# 03_cizgi_sensoru.net
KiCad netlist of a schematic drawn in EAGLE
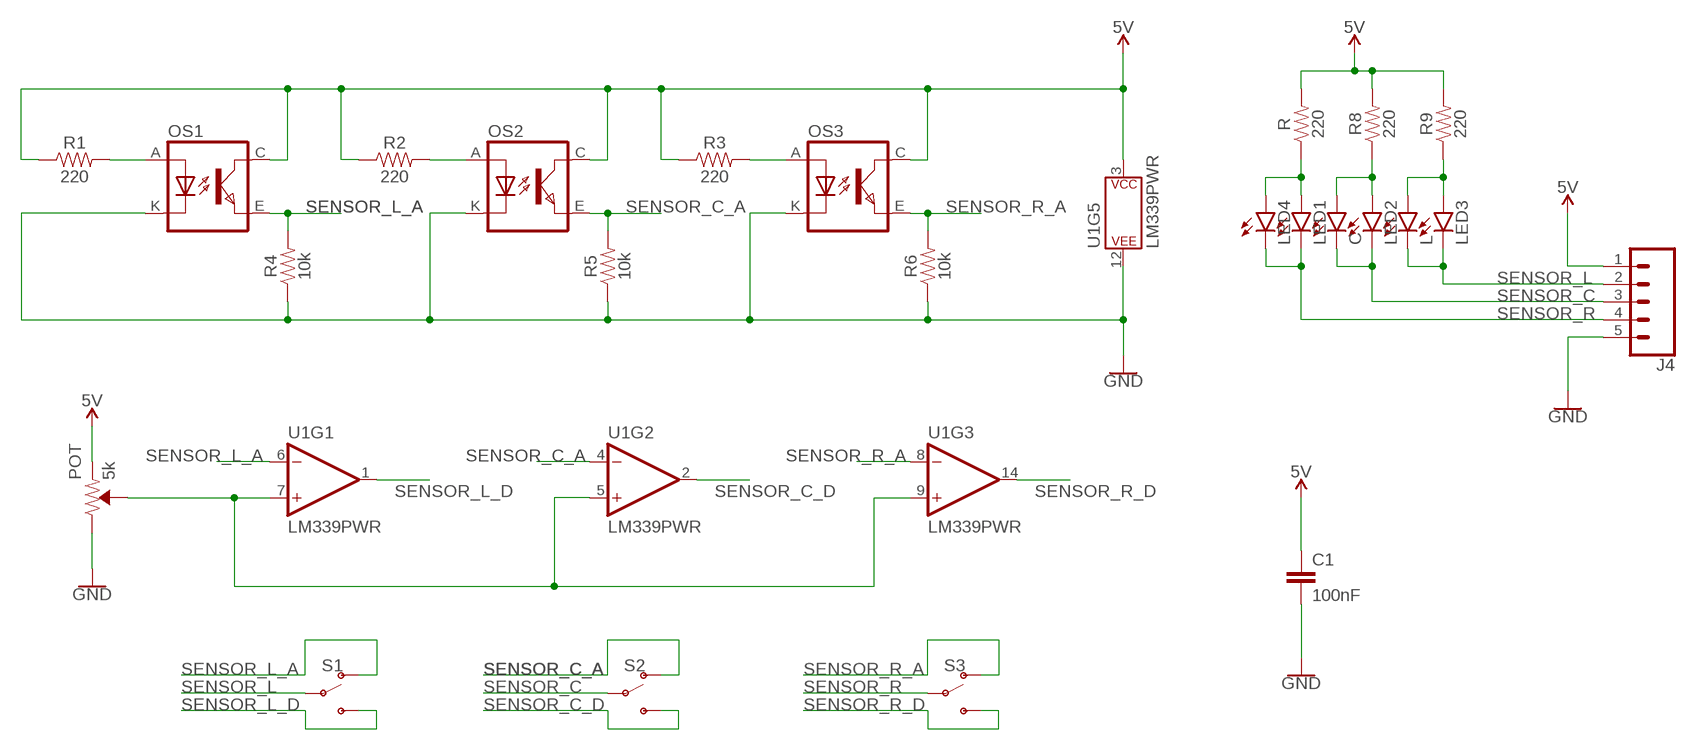
[diagram p0: schematic, sheet 1]

(export (version "E")
  (design (tool "Eeschema 10.0.6"))
  (components
    (comp (ref "C")
      (value "LEDSML0805")
      (footprint "eagle-import:SML0805")
      (libsource (lib "eagle-import") (part "LEDSML0805"))
    )
    (comp (ref "C1")
      (value "100nF")
      (footprint "eagle-import:0805")
      (libsource (lib "eagle-import") (part "0.33UF/330NF-0805-50V-10%"))
    )
    (comp (ref "J4")
      (value "CONN_05")
      (footprint "eagle-import:1X05")
      (libsource (lib "eagle-import") (part "CONN_05"))
    )
    (comp (ref "L")
      (value "LEDSML0805")
      (footprint "eagle-import:SML0805")
      (libsource (lib "eagle-import") (part "LEDSML0805"))
    )
    (comp (ref "LED1")
      (value "LEDSML0805")
      (footprint "eagle-import:SML0805")
      (libsource (lib "eagle-import") (part "LEDSML0805"))
    )
    (comp (ref "LED2")
      (value "LEDSML0805")
      (footprint "eagle-import:SML0805")
      (libsource (lib "eagle-import") (part "LEDSML0805"))
    )
    (comp (ref "LED3")
      (value "LEDSML0805")
      (footprint "eagle-import:SML0805")
      (libsource (lib "eagle-import") (part "LEDSML0805"))
    )
    (comp (ref "LED4")
      (value "LEDSML0805")
      (footprint "eagle-import:SML0805")
      (libsource (lib "eagle-import") (part "LEDSML0805"))
    )
    (comp (ref "OS1")
      (value "TCRT5000")
      (footprint "eagle-import:TCRT5000")
      (libsource (lib "eagle-import") (part "TCRT5000"))
    )
    (comp (ref "OS2")
      (value "TCRT5000")
      (footprint "eagle-import:TCRT5000")
      (libsource (lib "eagle-import") (part "TCRT5000"))
    )
    (comp (ref "OS3")
      (value "TCRT5000")
      (footprint "eagle-import:TCRT5000")
      (libsource (lib "eagle-import") (part "TCRT5000"))
    )
    (comp (ref "POT")
      (value "5k")
      (footprint "eagle-import:TRIMPOT-SMD-5MM")
      (libsource (lib "eagle-import") (part "TRIMPOT-SMD-5MM-CLOSED-1/4W-20%"))
    )
    (comp (ref "R")
      (value "220")
      (footprint "eagle-import:0805")
      (libsource (lib "eagle-import") (part "0.22OHM-0805-1/4W-1%"))
    )
    (comp (ref "R1")
      (value "220")
      (footprint "eagle-import:0805")
      (libsource (lib "eagle-import") (part "0.22OHM-0805-1/4W-1%"))
    )
    (comp (ref "R2")
      (value "220")
      (footprint "eagle-import:0805")
      (libsource (lib "eagle-import") (part "0.22OHM-0805-1/4W-1%"))
    )
    (comp (ref "R3")
      (value "220")
      (footprint "eagle-import:0805")
      (libsource (lib "eagle-import") (part "0.22OHM-0805-1/4W-1%"))
    )
    (comp (ref "R4")
      (value "10k")
      (footprint "eagle-import:0805")
      (libsource (lib "eagle-import") (part "0.22OHM-0805-1/4W-1%"))
    )
    (comp (ref "R5")
      (value "10k")
      (footprint "eagle-import:0805")
      (libsource (lib "eagle-import") (part "0.22OHM-0805-1/4W-1%"))
    )
    (comp (ref "R6")
      (value "10k")
      (footprint "eagle-import:0805")
      (libsource (lib "eagle-import") (part "0.22OHM-0805-1/4W-1%"))
    )
    (comp (ref "R8")
      (value "220")
      (footprint "eagle-import:0805")
      (libsource (lib "eagle-import") (part "0.22OHM-0805-1/4W-1%"))
    )
    (comp (ref "R9")
      (value "220")
      (footprint "eagle-import:0805")
      (libsource (lib "eagle-import") (part "0.22OHM-0805-1/4W-1%"))
    )
    (comp (ref "S1")
      (value "SWITCH-SPDT-SMD-RIGHT-ANGLE")
      (footprint "eagle-import:SWITCH_SPST_SMD_A")
      (libsource (lib "eagle-import") (part "SWITCH-SPDT-SMD-RIGHT-ANGLE"))
    )
    (comp (ref "S2")
      (value "SWITCH-SPDT-SMD-RIGHT-ANGLE")
      (footprint "eagle-import:SWITCH_SPST_SMD_A")
      (libsource (lib "eagle-import") (part "SWITCH-SPDT-SMD-RIGHT-ANGLE"))
    )
    (comp (ref "S3")
      (value "SWITCH-SPDT-SMD-RIGHT-ANGLE")
      (footprint "eagle-import:SWITCH_SPST_SMD_A")
      (libsource (lib "eagle-import") (part "SWITCH-SPDT-SMD-RIGHT-ANGLE"))
    )
    (comp (ref "U1")
      (value "LM339PWR")
      (footprint "eagle-import:TSSOP-14")
      (libsource (lib "eagle-import") (part "LM339"))
    )
  )
  (nets
    (net (code "1") (name "/SENSOR_C") (class "Default")
      (node (ref "C") (pin "C") (pinfunction "C_C") (pintype "passive"))
      (node (ref "J4") (pin "3") (pinfunction "3_3") (pintype "passive"))
      (node (ref "LED2") (pin "C") (pinfunction "C_C") (pintype "passive"))
      (node (ref "S2") (pin "2") (pinfunction "P_2") (pintype "passive"))
    )
    (net (code "2") (name "/SENSOR_C_A") (class "Default")
      (node (ref "OS2") (pin "E") (pinfunction "EMITTER_E") (pintype "passive"))
      (node (ref "R5") (pin "2") (pinfunction "2_2") (pintype "passive"))
      (node (ref "S2") (pin "1") (pinfunction "O_1") (pintype "passive"))
      (node (ref "U1") (pin "4") (pinfunction "-IN_4") (pintype "input"))
    )
    (net (code "3") (name "/SENSOR_C_D") (class "Default")
      (node (ref "S2") (pin "3") (pinfunction "S_3") (pintype "passive"))
      (node (ref "U1") (pin "2") (pinfunction "OUT_2") (pintype "output"))
    )
    (net (code "4") (name "/SENSOR_L") (class "Default")
      (node (ref "J4") (pin "2") (pinfunction "2_2") (pintype "passive"))
      (node (ref "L") (pin "C") (pinfunction "C_C") (pintype "passive"))
      (node (ref "LED3") (pin "C") (pinfunction "C_C") (pintype "passive"))
      (node (ref "S1") (pin "2") (pinfunction "P_2") (pintype "passive"))
    )
    (net (code "5") (name "/SENSOR_L_A") (class "Default")
      (node (ref "OS1") (pin "E") (pinfunction "EMITTER_E") (pintype "passive"))
      (node (ref "R4") (pin "2") (pinfunction "2_2") (pintype "passive"))
      (node (ref "S1") (pin "1") (pinfunction "O_1") (pintype "passive"))
      (node (ref "U1") (pin "6") (pinfunction "-IN_6") (pintype "input"))
    )
    (net (code "6") (name "/SENSOR_L_D") (class "Default")
      (node (ref "S1") (pin "3") (pinfunction "S_3") (pintype "passive"))
      (node (ref "U1") (pin "1") (pinfunction "OUT_1") (pintype "output"))
    )
    (net (code "7") (name "/SENSOR_R") (class "Default")
      (node (ref "J4") (pin "4") (pinfunction "4_4") (pintype "passive"))
      (node (ref "LED1") (pin "C") (pinfunction "C_C") (pintype "passive"))
      (node (ref "LED4") (pin "C") (pinfunction "C_C") (pintype "passive"))
      (node (ref "S3") (pin "2") (pinfunction "P_2") (pintype "passive"))
    )
    (net (code "8") (name "/SENSOR_R_A") (class "Default")
      (node (ref "OS3") (pin "E") (pinfunction "EMITTER_E") (pintype "passive"))
      (node (ref "R6") (pin "2") (pinfunction "2_2") (pintype "passive"))
      (node (ref "S3") (pin "1") (pinfunction "O_1") (pintype "passive"))
      (node (ref "U1") (pin "8") (pinfunction "-IN_8") (pintype "input"))
    )
    (net (code "9") (name "/SENSOR_R_D") (class "Default")
      (node (ref "S3") (pin "3") (pinfunction "S_3") (pintype "passive"))
      (node (ref "U1") (pin "14") (pinfunction "OUT_14") (pintype "output"))
    )
    (net (code "10") (name "5V") (class "Default")
      (node (ref "C1") (pin "1") (pinfunction "1_1") (pintype "passive"))
      (node (ref "J4") (pin "1") (pinfunction "1_1") (pintype "passive"))
      (node (ref "OS1") (pin "C") (pinfunction "COLLECTOR_C") (pintype "passive"))
      (node (ref "OS2") (pin "C") (pinfunction "COLLECTOR_C") (pintype "passive"))
      (node (ref "OS3") (pin "C") (pinfunction "COLLECTOR_C") (pintype "passive"))
      (node (ref "POT") (pin "A") (pinfunction "CCW_A") (pintype "passive"))
      (node (ref "R") (pin "2") (pinfunction "2_2") (pintype "passive"))
      (node (ref "R1") (pin "1") (pinfunction "1_1") (pintype "passive"))
      (node (ref "R2") (pin "1") (pinfunction "1_1") (pintype "passive"))
      (node (ref "R3") (pin "1") (pinfunction "1_1") (pintype "passive"))
      (node (ref "R8") (pin "2") (pinfunction "2_2") (pintype "passive"))
      (node (ref "R9") (pin "2") (pinfunction "2_2") (pintype "passive"))
      (node (ref "U1") (pin "3") (pinfunction "P$V+_3") (pintype "bidirectional"))
    )
    (net (code "11") (name "GND") (class "Default")
      (node (ref "C1") (pin "2") (pinfunction "2_2") (pintype "passive"))
      (node (ref "J4") (pin "5") (pinfunction "5_5") (pintype "passive"))
      (node (ref "OS1") (pin "K") (pinfunction "CATHODE_K") (pintype "passive"))
      (node (ref "OS2") (pin "K") (pinfunction "CATHODE_K") (pintype "passive"))
      (node (ref "OS3") (pin "K") (pinfunction "CATHODE_K") (pintype "passive"))
      (node (ref "POT") (pin "C") (pinfunction "CW_C") (pintype "passive"))
      (node (ref "R4") (pin "1") (pinfunction "1_1") (pintype "passive"))
      (node (ref "R5") (pin "1") (pinfunction "1_1") (pintype "passive"))
      (node (ref "R6") (pin "1") (pinfunction "1_1") (pintype "passive"))
      (node (ref "U1") (pin "12") (pinfunction "P$V-_12") (pintype "bidirectional"))
    )
    (net (code "12") (name "Net-(C-PadA)") (class "Default")
      (node (ref "C") (pin "A") (pinfunction "A_A") (pintype "passive"))
      (node (ref "LED2") (pin "A") (pinfunction "A_A") (pintype "passive"))
      (node (ref "R8") (pin "1") (pinfunction "1_1") (pintype "passive"))
    )
    (net (code "13") (name "Net-(L-PadA)") (class "Default")
      (node (ref "L") (pin "A") (pinfunction "A_A") (pintype "passive"))
      (node (ref "LED3") (pin "A") (pinfunction "A_A") (pintype "passive"))
      (node (ref "R9") (pin "1") (pinfunction "1_1") (pintype "passive"))
    )
    (net (code "14") (name "Net-(LED1-PadA)") (class "Default")
      (node (ref "LED1") (pin "A") (pinfunction "A_A") (pintype "passive"))
      (node (ref "LED4") (pin "A") (pinfunction "A_A") (pintype "passive"))
      (node (ref "R") (pin "1") (pinfunction "1_1") (pintype "passive"))
    )
    (net (code "15") (name "Net-(OS1-ANODE)") (class "Default")
      (node (ref "OS1") (pin "A") (pinfunction "ANODE_A") (pintype "passive"))
      (node (ref "R1") (pin "2") (pinfunction "2_2") (pintype "passive"))
    )
    (net (code "16") (name "Net-(OS2-ANODE)") (class "Default")
      (node (ref "OS2") (pin "A") (pinfunction "ANODE_A") (pintype "passive"))
      (node (ref "R2") (pin "2") (pinfunction "2_2") (pintype "passive"))
    )
    (net (code "17") (name "Net-(OS3-ANODE)") (class "Default")
      (node (ref "OS3") (pin "A") (pinfunction "ANODE_A") (pintype "passive"))
      (node (ref "R3") (pin "2") (pinfunction "2_2") (pintype "passive"))
    )
    (net (code "18") (name "Net-(POT-WIPER)") (class "Default")
      (node (ref "POT") (pin "B") (pinfunction "WIPER_B") (pintype "passive"))
      (node (ref "U1") (pin "5") (pinfunction "+IN_5") (pintype "input"))
      (node (ref "U1") (pin "7") (pinfunction "+IN_7") (pintype "input"))
      (node (ref "U1") (pin "9") (pinfunction "+IN_9") (pintype "input"))
    )
  )
)
